# JTAG20-JTAG9.net
KiCad netlist of a schematic drawn in Altium Designer
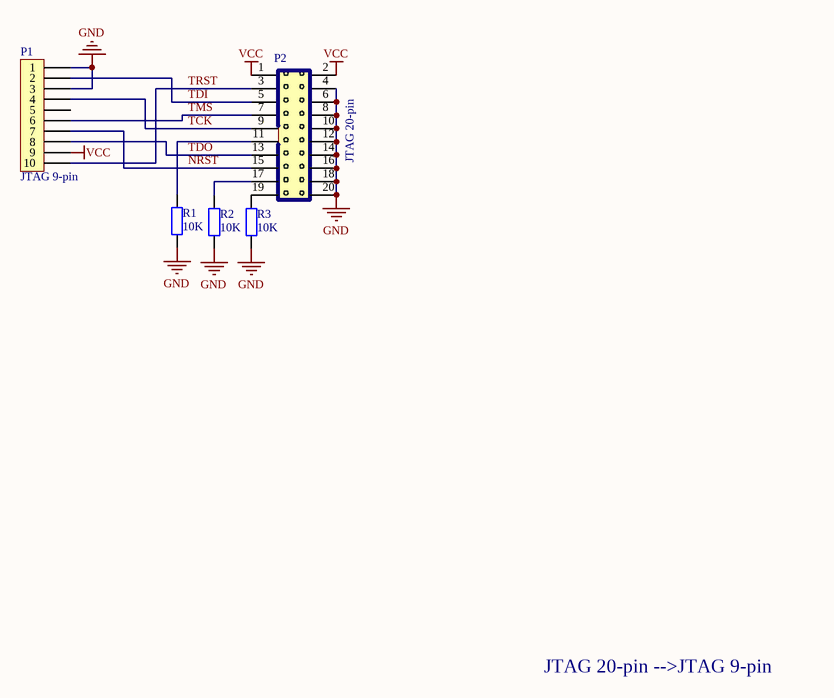
[diagram p0: JTAG20-JTAG9.SchDoc]

(export (version "E")
  (design (tool "Eeschema 10.0.6"))
  (components
    (comp (ref "P1") (value "JTAG 9-pin") (footprint "PBD-10R") (libsource (lib "NEW") (part "PBD-10R")))
    (comp (ref "P2") (value "JTAG 20-pin") (footprint "IDC-20M") (libsource (lib "NEW") (part "IDC-20M")))
    (comp (ref "R1")
      (value "10K")
      (footprint "C0603")
      (description "Resistor")
      (fields (field (name "Comment") "RES"))
      (libsource (lib "NEW") (part "RES"))
    )
    (comp (ref "R2")
      (value "10K")
      (footprint "C0603")
      (description "Resistor")
      (fields (field (name "Comment") "RES"))
      (libsource (lib "NEW") (part "RES"))
    )
    (comp (ref "R3")
      (value "10K")
      (footprint "C0603")
      (description "Resistor")
      (fields (field (name "Comment") "RES"))
      (libsource (lib "NEW") (part "RES"))
    )
  )
  (nets
    (net (code "1") (name "/NRST") (class "Default")
      (node (ref "P1") (pin "7") (pinfunction "7_7") (pintype "passive"))
      (node (ref "P2") (pin "15") (pinfunction "15_15") (pintype "passive"))
    )
    (net (code "2") (name "/TCK") (class "Default")
      (node (ref "P1") (pin "4") (pinfunction "4_4") (pintype "passive"))
      (node (ref "P2") (pin "9") (pintype "passive"))
    )
    (net (code "3") (name "/TDI") (class "Default")
      (node (ref "P1") (pin "2") (pinfunction "2_2") (pintype "passive"))
      (node (ref "P2") (pin "5") (pintype "passive"))
    )
    (net (code "4") (name "/TDO") (class "Default")
      (node (ref "P1") (pin "8") (pinfunction "8_8") (pintype "passive"))
      (node (ref "P2") (pin "13") (pintype "passive"))
    )
    (net (code "5") (name "/TMS") (class "Default")
      (node (ref "P1") (pin "6") (pinfunction "6_6") (pintype "passive"))
      (node (ref "P2") (pin "7") (pintype "passive"))
    )
    (net (code "6") (name "/TRST") (class "Default")
      (node (ref "P1") (pin "10") (pinfunction "10_10") (pintype "passive"))
      (node (ref "P2") (pin "3") (pintype "passive"))
    )
    (net (code "7") (name "GND") (class "Default")
      (node (ref "P1") (pin "1") (pinfunction "1_1") (pintype "passive"))
      (node (ref "P1") (pin "3") (pinfunction "3_3") (pintype "passive"))
      (node (ref "P2") (pin "10") (pintype "passive"))
      (node (ref "P2") (pin "12") (pintype "passive"))
      (node (ref "P2") (pin "14") (pintype "passive"))
      (node (ref "P2") (pin "16") (pinfunction "16_16") (pintype "passive"))
      (node (ref "P2") (pin "18") (pinfunction "18_18") (pintype "passive"))
      (node (ref "P2") (pin "20") (pinfunction "20_20") (pintype "passive"))
      (node (ref "P2") (pin "4") (pintype "passive"))
      (node (ref "P2") (pin "6") (pintype "passive"))
      (node (ref "P2") (pin "8") (pintype "passive"))
      (node (ref "R1") (pin "1") (pinfunction "1_1") (pintype "passive"))
      (node (ref "R2") (pin "1") (pinfunction "1_1") (pintype "passive"))
      (node (ref "R3") (pin "1") (pinfunction "1_1") (pintype "passive"))
    )
    (net (code "8") (name "Net-(P2-Pad11)") (class "Default")
      (node (ref "P2") (pin "11") (pintype "passive"))
      (node (ref "R1") (pin "2") (pinfunction "2_2") (pintype "passive"))
    )
    (net (code "9") (name "Net-(P2-Pad17)") (class "Default")
      (node (ref "P2") (pin "17") (pinfunction "17_17") (pintype "passive"))
      (node (ref "R2") (pin "2") (pinfunction "2_2") (pintype "passive"))
    )
    (net (code "10") (name "Net-(P2-Pad19)") (class "Default")
      (node (ref "P2") (pin "19") (pinfunction "19_19") (pintype "passive"))
      (node (ref "R3") (pin "2") (pinfunction "2_2") (pintype "passive"))
    )
    (net (code "11") (name "VCC") (class "Default")
      (node (ref "P1") (pin "9") (pinfunction "9_9") (pintype "passive"))
      (node (ref "P2") (pin "1") (pintype "passive"))
      (node (ref "P2") (pin "2") (pintype "passive"))
    )
    (net (code "12") (name "unconnected-(P1-Pad5)") (class "Default")
      (node (ref "P1") (pin "5") (pinfunction "5_5") (pintype "passive"))
    )
  )
)
